# lcd-screen.net
KiCad netlist of a schematic drawn in EAGLE
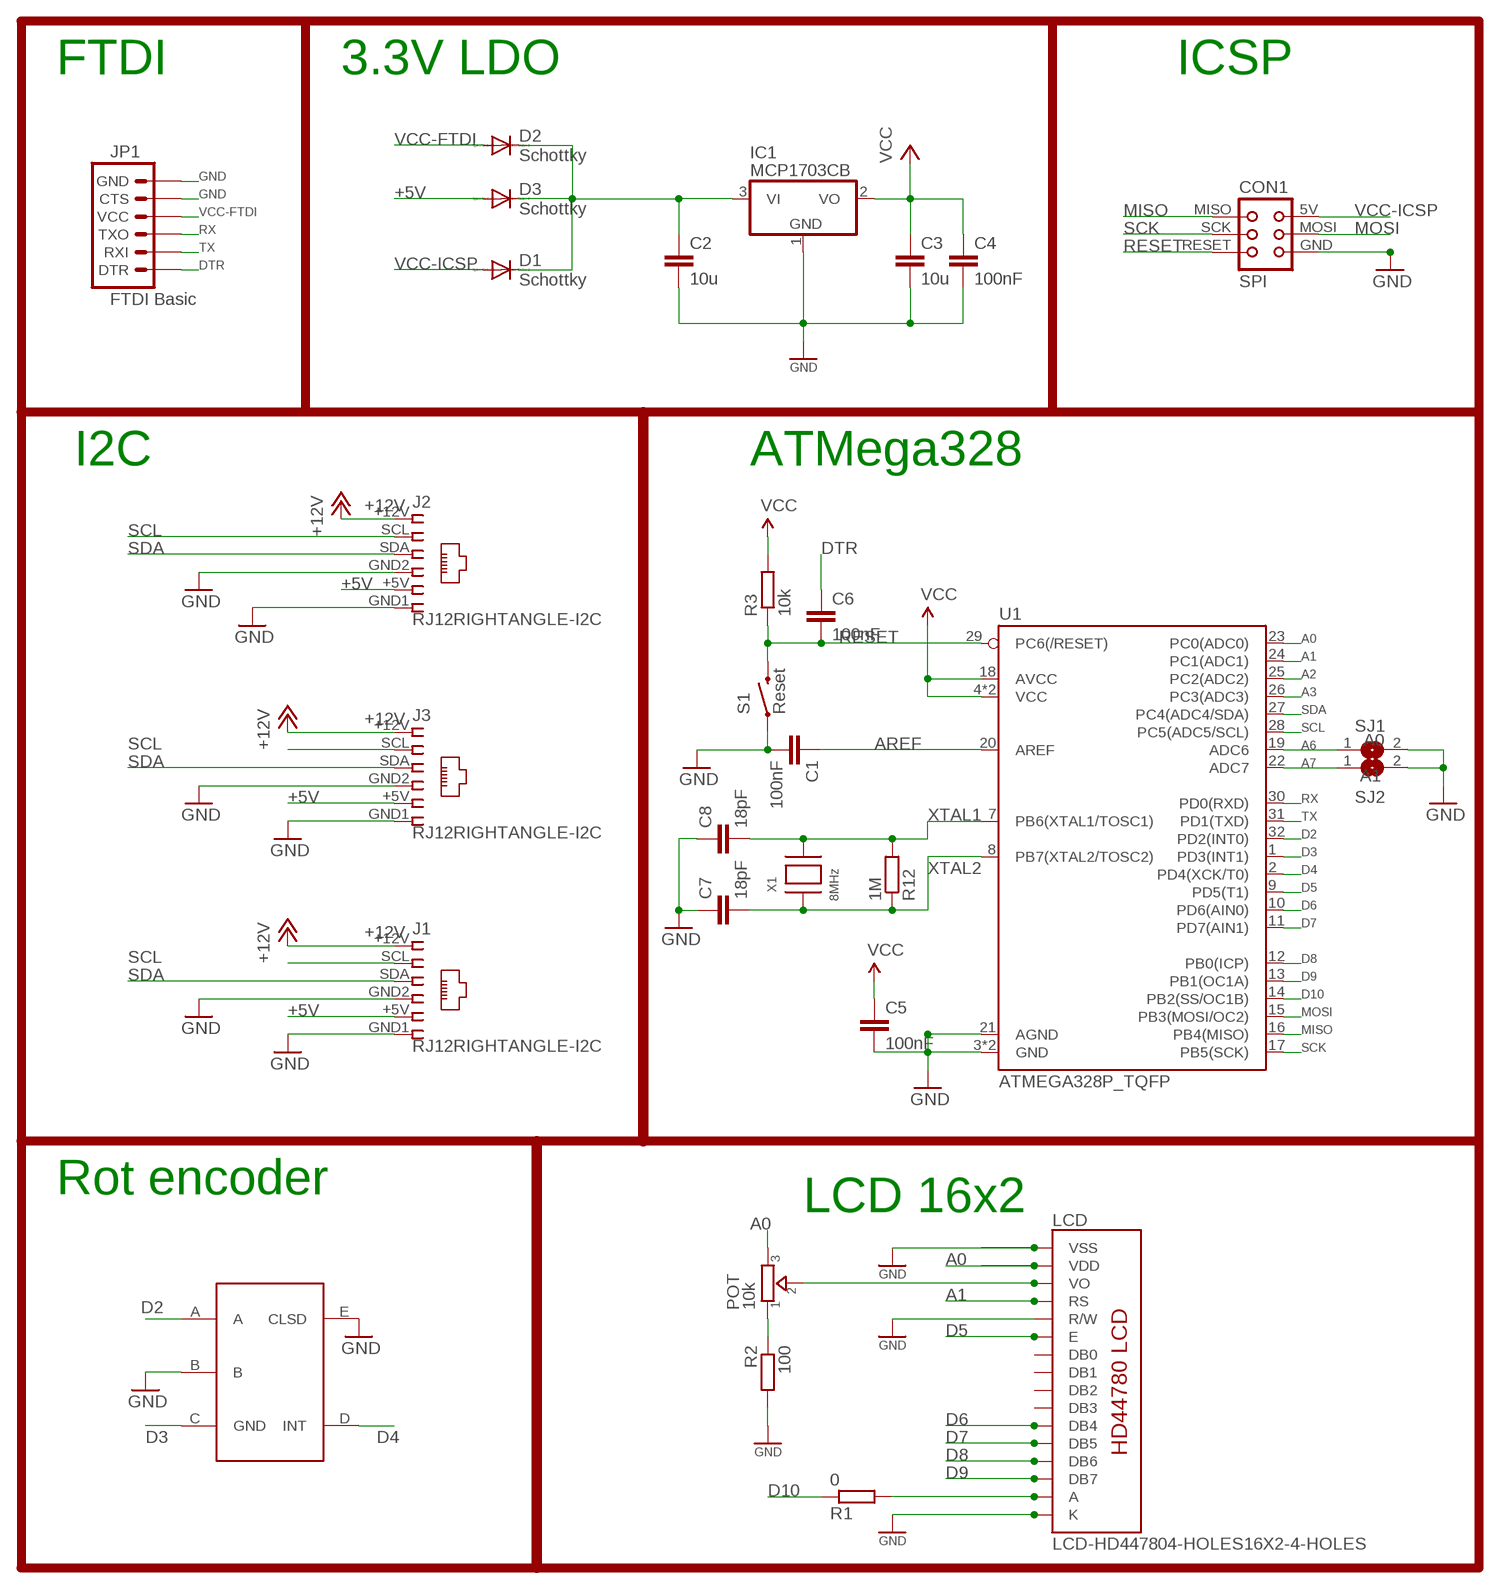
[diagram p0: schematic, sheet 1]

(export (version "E")
  (design (tool "Eeschema 10.0.6"))
  (components
    (comp (ref "C1")
      (value "100nF")
      (footprint "eagle-import:C0805K")
      (fields (field (name "MPN") "80-C1206C104K5R"))
      (libsource (lib "eagle-import") (part "C-EUC0805K"))
    )
    (comp (ref "C2")
      (value "10u")
      (footprint "eagle-import:C0805K")
      (fields (field (name "MPN") "77-VJ1206V106ZXQTBC"))
      (libsource (lib "eagle-import") (part "C-EUC0805K"))
    )
    (comp (ref "C3")
      (value "10u")
      (footprint "eagle-import:C0805K")
      (fields (field (name "MPN") "77-VJ1206V106ZXQTBC"))
      (libsource (lib "eagle-import") (part "C-EUC0805K"))
    )
    (comp (ref "C4")
      (value "100nF")
      (footprint "eagle-import:C0805K")
      (fields (field (name "MPN") "80-C1206C104K5R"))
      (libsource (lib "eagle-import") (part "C-EUC0805K"))
    )
    (comp (ref "C5")
      (value "100nF")
      (footprint "eagle-import:C0805K")
      (fields (field (name "MPN") "80-C1206C104K5R"))
      (libsource (lib "eagle-import") (part "C-EUC0805K"))
    )
    (comp (ref "C6")
      (value "100nF")
      (footprint "eagle-import:C0805K")
      (fields (field (name "MPN") "80-C1206C104K5R"))
      (libsource (lib "eagle-import") (part "C-EUC0805K"))
    )
    (comp (ref "C7")
      (value "18pF")
      (footprint "eagle-import:C0805K")
      (fields (field (name "MPN") "77-VJ1206A180JXXPBC"))
      (libsource (lib "eagle-import") (part "C-EUC0805K"))
    )
    (comp (ref "C8")
      (value "18pF")
      (footprint "eagle-import:C0805K")
      (fields (field (name "MPN") "77-VJ1206A180JXXPBC"))
      (libsource (lib "eagle-import") (part "C-EUC0805K"))
    )
    (comp (ref "CON1")
      (value "SPI")
      (footprint "eagle-import:TC2030-MCP")
      (libsource (lib "eagle-import") (part "TINYISPTAG"))
    )
    (comp (ref "D1")
      (value "Schottky")
      (footprint "eagle-import:SOD123")
      (fields (field (name "MPN") "621-1N5819HW-F"))
      (libsource (lib "eagle-import") (part "MBR0520LT"))
    )
    (comp (ref "D2")
      (value "Schottky")
      (footprint "eagle-import:SOD123")
      (fields (field (name "MPN") "621-1N5819HW-F"))
      (libsource (lib "eagle-import") (part "MBR0520LT"))
    )
    (comp (ref "D3")
      (value "Schottky")
      (footprint "eagle-import:SOD123")
      (fields (field (name "MPN") "621-1N5819HW-F"))
      (libsource (lib "eagle-import") (part "MBR0520LT"))
    )
    (comp (ref "IC1")
      (value "MCP1703CB")
      (footprint "eagle-import:SOT23")
      (libsource (lib "eagle-import") (part "MCP1703CB"))
    )
    (comp (ref "J1")
      (value "RJ12RIGHTANGLE-I2C")
      (footprint "eagle-import:RJ12-RIGHTANGLE-I2C")
      (libsource (lib "eagle-import") (part "RJ12RIGHTANGLE-I2C"))
    )
    (comp (ref "J2")
      (value "RJ12RIGHTANGLE-I2C")
      (footprint "eagle-import:RJ12-RIGHTANGLE-I2C")
      (libsource (lib "eagle-import") (part "RJ12RIGHTANGLE-I2C"))
    )
    (comp (ref "J3")
      (value "RJ12RIGHTANGLE-I2C")
      (footprint "eagle-import:RJ12-RIGHTANGLE-I2C")
      (libsource (lib "eagle-import") (part "RJ12RIGHTANGLE-I2C"))
    )
    (comp (ref "JP1")
      (value "FTDI Basic")
      (footprint "eagle-import:1X06")
      (libsource (lib "eagle-import") (part "ARDUINO_SERIAL_PROGRAMPTH"))
    )
    (comp (ref "LCD")
      (value "LCD-HD447804-HOLES16X2-4-HOLES")
      (footprint "eagle-import:LCD-16X2-4HOLES")
      (libsource (lib "eagle-import") (part "LCD-HD4478016X2-4-HOLES4-HOLES"))
    )
    (comp (ref "POT")
      (value "10k")
      (footprint "eagle-import:TRIMMER_3362P")
      (libsource (lib "eagle-import") (part "TRIMMER-3362P"))
    )
    (comp (ref "R1")
      (value "0")
      (footprint "eagle-import:R0805")
      (libsource (lib "eagle-import") (part "rcl_334_R-EU_R0805"))
    )
    (comp (ref "R2")
      (value "100")
      (footprint "eagle-import:R0805")
      (libsource (lib "eagle-import") (part "R-EU_R0805"))
    )
    (comp (ref "R3")
      (value "10k")
      (footprint "eagle-import:R0805")
      (libsource (lib "eagle-import") (part "R-EU_R0805"))
    )
    (comp (ref "R12")
      (value "1M")
      (footprint "eagle-import:R0805")
      (libsource (lib "eagle-import") (part "R-EU_R0805"))
    )
    (comp (ref "S1")
      (value "Reset")
      (footprint "eagle-import:TACTILE-SWITCH-SMD-ALT01")
      (libsource (lib "eagle-import") (part "SWITCH-MOMENTARY-2SMD-ALT01"))
    )
    (comp (ref "SJ1") (value "A0") (footprint "eagle-import:SJ") (libsource (lib "eagle-import") (part "SJ")))
    (comp (ref "SJ2") (value "A1") (footprint "eagle-import:SJ") (libsource (lib "eagle-import") (part "SJ")))
    (comp (ref "U$1")
      (value "EC11E")
      (footprint "eagle-import:EC11E")
      (libsource (lib "eagle-import") (part "EC11E"))
    )
    (comp (ref "U1")
      (value "ATMEGA328P_TQFP")
      (footprint "eagle-import:TQFP32-08")
      (libsource (lib "eagle-import") (part "ATMEGA328P_TQFP"))
    )
    (comp (ref "X1")
      (value "8MHz")
      (footprint "eagle-import:NX6035")
      (fields (field (name "MPN") "729-F60800010"))
      (libsource (lib "eagle-import") (part "XTALNX6035"))
    )
  )
  (nets
    (net (code "1") (name "+12V") (class "Default")
      (node (ref "J1") (pin "+12V") (pinfunction "1_+12V") (pintype "bidirectional"))
      (node (ref "J2") (pin "+12V") (pinfunction "1_+12V") (pintype "bidirectional"))
      (node (ref "J3") (pin "+12V") (pinfunction "1_+12V") (pintype "bidirectional"))
    )
    (net (code "2") (name "/+5V") (class "Default")
      (node (ref "D3") (pin "A") (pinfunction "A_A") (pintype "passive"))
      (node (ref "J1") (pin "+5V") (pinfunction "5_+5V") (pintype "bidirectional"))
      (node (ref "J2") (pin "+5V") (pinfunction "5_+5V") (pintype "bidirectional"))
      (node (ref "J3") (pin "+5V") (pinfunction "5_+5V") (pintype "bidirectional"))
    )
    (net (code "3") (name "/A0") (class "Default")
      (node (ref "LCD") (pin "2") (pinfunction "VDD_2") (pintype "power_in"))
      (node (ref "POT") (pin "3") (pinfunction "3_3") (pintype "passive"))
      (node (ref "U1") (pin "23") (pinfunction "PC0(ADC0)_23") (pintype "bidirectional"))
    )
    (net (code "4") (name "/A1") (class "Default")
      (node (ref "LCD") (pin "4") (pinfunction "RS_4") (pintype "input"))
      (node (ref "U1") (pin "24") (pinfunction "PC1(ADC1)_24") (pintype "bidirectional"))
    )
    (net (code "5") (name "/A2") (class "Default")
      (node (ref "U1") (pin "25") (pinfunction "PC2(ADC2)_25") (pintype "bidirectional"))
    )
    (net (code "6") (name "/A3") (class "Default")
      (node (ref "U1") (pin "26") (pinfunction "PC3(ADC3)_26") (pintype "bidirectional"))
    )
    (net (code "7") (name "/A6") (class "Default")
      (node (ref "SJ1") (pin "1") (pinfunction "1_1") (pintype "passive"))
      (node (ref "U1") (pin "19") (pinfunction "ADC6_19") (pintype "bidirectional"))
    )
    (net (code "8") (name "/A7") (class "Default")
      (node (ref "SJ2") (pin "1") (pinfunction "1_1") (pintype "passive"))
      (node (ref "U1") (pin "22") (pinfunction "ADC7_22") (pintype "bidirectional"))
    )
    (net (code "9") (name "/AREF") (class "Default")
      (node (ref "C1") (pin "1") (pinfunction "1_1") (pintype "passive"))
      (node (ref "U1") (pin "20") (pinfunction "AREF_20") (pintype "bidirectional"))
    )
    (net (code "10") (name "/D2") (class "Default")
      (node (ref "U$1") (pin "A") (pinfunction "A_A") (pintype "bidirectional"))
      (node (ref "U1") (pin "32") (pinfunction "PD2(INT0)_32") (pintype "bidirectional"))
    )
    (net (code "11") (name "/D3") (class "Default")
      (node (ref "U$1") (pin "C") (pinfunction "GND_C") (pintype "bidirectional"))
      (node (ref "U1") (pin "1") (pinfunction "PD3(INT1)_1") (pintype "bidirectional"))
    )
    (net (code "12") (name "/D4") (class "Default")
      (node (ref "U$1") (pin "D") (pinfunction "INT_D") (pintype "bidirectional"))
      (node (ref "U1") (pin "2") (pinfunction "PD4(XCK/T0)_2") (pintype "bidirectional"))
    )
    (net (code "13") (name "/D5") (class "Default")
      (node (ref "LCD") (pin "6") (pinfunction "E_6") (pintype "input"))
      (node (ref "U1") (pin "9") (pinfunction "PD5(T1)_9") (pintype "bidirectional"))
    )
    (net (code "14") (name "/D6") (class "Default")
      (node (ref "LCD") (pin "11") (pinfunction "DB4_11") (pintype "bidirectional"))
      (node (ref "U1") (pin "10") (pinfunction "PD6(AIN0)_10") (pintype "bidirectional"))
    )
    (net (code "15") (name "/D7") (class "Default")
      (node (ref "LCD") (pin "12") (pinfunction "DB5_12") (pintype "bidirectional"))
      (node (ref "U1") (pin "11") (pinfunction "PD7(AIN1)_11") (pintype "bidirectional"))
    )
    (net (code "16") (name "/D8") (class "Default")
      (node (ref "LCD") (pin "13") (pinfunction "DB6_13") (pintype "bidirectional"))
      (node (ref "U1") (pin "12") (pinfunction "PB0(ICP)_12") (pintype "bidirectional"))
    )
    (net (code "17") (name "/D9") (class "Default")
      (node (ref "LCD") (pin "14") (pinfunction "DB7_14") (pintype "bidirectional"))
      (node (ref "U1") (pin "13") (pinfunction "PB1(OC1A)_13") (pintype "bidirectional"))
    )
    (net (code "18") (name "/D10") (class "Default")
      (node (ref "R1") (pin "1") (pinfunction "1_1") (pintype "passive"))
      (node (ref "U1") (pin "14") (pinfunction "PB2(SS/OC1B)_14") (pintype "bidirectional"))
    )
    (net (code "19") (name "/DTR") (class "Default")
      (node (ref "C6") (pin "1") (pinfunction "1_1") (pintype "passive"))
      (node (ref "JP1") (pin "1") (pinfunction "DTR_1") (pintype "passive"))
    )
    (net (code "20") (name "/MISO") (class "Default")
      (node (ref "CON1") (pin "MISO") (pinfunction "MISO_MISO") (pintype "passive"))
      (node (ref "U1") (pin "16") (pinfunction "PB4(MISO)_16") (pintype "bidirectional"))
    )
    (net (code "21") (name "/MOSI") (class "Default")
      (node (ref "CON1") (pin "MOSI") (pinfunction "MOSI_MOSI") (pintype "passive"))
      (node (ref "U1") (pin "15") (pinfunction "PB3(MOSI/OC2)_15") (pintype "bidirectional"))
    )
    (net (code "22") (name "/RESET") (class "Default")
      (node (ref "C6") (pin "2") (pinfunction "2_2") (pintype "passive"))
      (node (ref "CON1") (pin "RESET") (pinfunction "RESET_RESET") (pintype "passive"))
      (node (ref "R3") (pin "1") (pinfunction "1_1") (pintype "passive"))
      (node (ref "S1") (pin "3") (pinfunction "2_3") (pintype "passive"))
      (node (ref "S1") (pin "4") (pinfunction "2_4") (pintype "passive"))
      (node (ref "U1") (pin "29") (pinfunction "PC6(/RESET)_29") (pintype "bidirectional"))
    )
    (net (code "23") (name "/RX") (class "Default")
      (node (ref "JP1") (pin "3") (pinfunction "TXO_3") (pintype "passive"))
      (node (ref "U1") (pin "30") (pinfunction "PD0(RXD)_30") (pintype "bidirectional"))
    )
    (net (code "24") (name "/SCK") (class "Default")
      (node (ref "CON1") (pin "SCK") (pinfunction "SCK_SCK") (pintype "passive"))
      (node (ref "U1") (pin "17") (pinfunction "PB5(SCK)_17") (pintype "bidirectional"))
    )
    (net (code "25") (name "/SCL") (class "Default")
      (node (ref "J1") (pin "SCL") (pinfunction "2_SCL") (pintype "bidirectional"))
      (node (ref "J2") (pin "SCL") (pinfunction "2_SCL") (pintype "bidirectional"))
      (node (ref "J3") (pin "SCL") (pinfunction "2_SCL") (pintype "bidirectional"))
      (node (ref "U1") (pin "28") (pinfunction "PC5(ADC5/SCL)_28") (pintype "bidirectional"))
    )
    (net (code "26") (name "/SDA") (class "Default")
      (node (ref "J1") (pin "SDA") (pinfunction "3_SDA") (pintype "bidirectional"))
      (node (ref "J2") (pin "SDA") (pinfunction "3_SDA") (pintype "bidirectional"))
      (node (ref "J3") (pin "SDA") (pinfunction "3_SDA") (pintype "bidirectional"))
      (node (ref "U1") (pin "27") (pinfunction "PC4(ADC4/SDA)_27") (pintype "bidirectional"))
    )
    (net (code "27") (name "/TX") (class "Default")
      (node (ref "JP1") (pin "2") (pinfunction "RXI_2") (pintype "passive"))
      (node (ref "U1") (pin "31") (pinfunction "PD1(TXD)_31") (pintype "bidirectional"))
    )
    (net (code "28") (name "/VCC-FTDI") (class "Default")
      (node (ref "D2") (pin "A") (pinfunction "A_A") (pintype "passive"))
      (node (ref "JP1") (pin "4") (pinfunction "VCC_4") (pintype "passive"))
    )
    (net (code "29") (name "/VCC-ICSP") (class "Default")
      (node (ref "CON1") (pin "5V") (pinfunction "VCC_5V") (pintype "passive"))
      (node (ref "D1") (pin "A") (pinfunction "A_A") (pintype "passive"))
    )
    (net (code "30") (name "/XTAL1") (class "Default")
      (node (ref "C8") (pin "2") (pinfunction "2_2") (pintype "passive"))
      (node (ref "R12") (pin "2") (pinfunction "2_2") (pintype "passive"))
      (node (ref "U1") (pin "7") (pinfunction "PB6(XTAL1/TOSC1)_7") (pintype "bidirectional"))
      (node (ref "X1") (pin "P$2") (pinfunction "P$2_P$2") (pintype "bidirectional"))
    )
    (net (code "31") (name "/XTAL2") (class "Default")
      (node (ref "C7") (pin "2") (pinfunction "2_2") (pintype "passive"))
      (node (ref "R12") (pin "1") (pinfunction "1_1") (pintype "passive"))
      (node (ref "U1") (pin "8") (pinfunction "PB7(XTAL2/TOSC2)_8") (pintype "bidirectional"))
      (node (ref "X1") (pin "P$1") (pinfunction "P$1_P$1") (pintype "bidirectional"))
    )
    (net (code "32") (name "GND") (class "Default")
      (node (ref "C1") (pin "2") (pinfunction "2_2") (pintype "passive"))
      (node (ref "C2") (pin "2") (pinfunction "2_2") (pintype "passive"))
      (node (ref "C3") (pin "2") (pinfunction "2_2") (pintype "passive"))
      (node (ref "C4") (pin "2") (pinfunction "2_2") (pintype "passive"))
      (node (ref "C5") (pin "2") (pinfunction "2_2") (pintype "passive"))
      (node (ref "C7") (pin "1") (pinfunction "1_1") (pintype "passive"))
      (node (ref "C8") (pin "1") (pinfunction "1_1") (pintype "passive"))
      (node (ref "CON1") (pin "GND") (pinfunction "GND_GND") (pintype "passive"))
      (node (ref "IC1") (pin "1") (pinfunction "GND_1") (pintype "passive"))
      (node (ref "J1") (pin "GND1") (pinfunction "6_GND1") (pintype "bidirectional"))
      (node (ref "J1") (pin "GND2") (pinfunction "4_GND2") (pintype "bidirectional"))
      (node (ref "J2") (pin "GND1") (pinfunction "6_GND1") (pintype "bidirectional"))
      (node (ref "J2") (pin "GND2") (pinfunction "4_GND2") (pintype "bidirectional"))
      (node (ref "J3") (pin "GND1") (pinfunction "6_GND1") (pintype "bidirectional"))
      (node (ref "J3") (pin "GND2") (pinfunction "4_GND2") (pintype "bidirectional"))
      (node (ref "JP1") (pin "5") (pinfunction "CTS_5") (pintype "passive"))
      (node (ref "JP1") (pin "6") (pinfunction "GND_6") (pintype "passive"))
      (node (ref "LCD") (pin "1") (pinfunction "VSS_1") (pintype "power_in"))
      (node (ref "LCD") (pin "16") (pinfunction "K_16") (pintype "power_in"))
      (node (ref "LCD") (pin "5") (pinfunction "R/W_5") (pintype "input"))
      (node (ref "R2") (pin "2") (pinfunction "2_2") (pintype "passive"))
      (node (ref "S1") (pin "1") (pinfunction "1_1") (pintype "passive"))
      (node (ref "S1") (pin "2") (pinfunction "1_2") (pintype "passive"))
      (node (ref "SJ1") (pin "2") (pinfunction "2_2") (pintype "passive"))
      (node (ref "SJ2") (pin "2") (pinfunction "2_2") (pintype "passive"))
      (node (ref "U$1") (pin "B") (pinfunction "B_B") (pintype "bidirectional"))
      (node (ref "U$1") (pin "E") (pinfunction "CLSD_E") (pintype "bidirectional"))
      (node (ref "U1") (pin "21") (pinfunction "AGND_21") (pintype "bidirectional"))
      (node (ref "U1") (pin "3") (pinfunction "GND_3") (pintype "bidirectional"))
      (node (ref "U1") (pin "5") (pinfunction "GND_5") (pintype "bidirectional"))
    )
    (net (code "33") (name "Net-(IC1-VI)") (class "Default")
      (node (ref "C2") (pin "1") (pinfunction "1_1") (pintype "passive"))
      (node (ref "D1") (pin "C") (pinfunction "C_C") (pintype "passive"))
      (node (ref "D2") (pin "C") (pinfunction "C_C") (pintype "passive"))
      (node (ref "D3") (pin "C") (pinfunction "C_C") (pintype "passive"))
      (node (ref "IC1") (pin "3") (pinfunction "VI_3") (pintype "input"))
    )
    (net (code "34") (name "Net-(LCD-A)") (class "Default")
      (node (ref "LCD") (pin "15") (pinfunction "A_15") (pintype "power_in"))
      (node (ref "R1") (pin "2") (pinfunction "2_2") (pintype "passive"))
    )
    (net (code "35") (name "Net-(LCD-VO)") (class "Default")
      (node (ref "LCD") (pin "3") (pinfunction "VO_3") (pintype "bidirectional"))
      (node (ref "POT") (pin "2") (pinfunction "2_2") (pintype "passive"))
    )
    (net (code "36") (name "Net-(POT-Pad1)") (class "Default")
      (node (ref "POT") (pin "1") (pinfunction "1_1") (pintype "passive"))
      (node (ref "R2") (pin "1") (pinfunction "1_1") (pintype "passive"))
    )
    (net (code "37") (name "VCC") (class "Default")
      (node (ref "C3") (pin "1") (pinfunction "1_1") (pintype "passive"))
      (node (ref "C4") (pin "1") (pinfunction "1_1") (pintype "passive"))
      (node (ref "C5") (pin "1") (pinfunction "1_1") (pintype "passive"))
      (node (ref "IC1") (pin "2") (pinfunction "VO_2") (pintype "passive"))
      (node (ref "R3") (pin "2") (pinfunction "2_2") (pintype "passive"))
      (node (ref "U1") (pin "18") (pinfunction "AVCC_18") (pintype "bidirectional"))
      (node (ref "U1") (pin "4") (pinfunction "VCC_4") (pintype "bidirectional"))
      (node (ref "U1") (pin "6") (pinfunction "VCC_6") (pintype "bidirectional"))
    )
    (net (code "38") (name "unconnected-(LCD-DB0-Pad7)") (class "Default")
      (node (ref "LCD") (pin "7") (pinfunction "DB0_7") (pintype "bidirectional"))
    )
    (net (code "39") (name "unconnected-(LCD-DB1-Pad8)") (class "Default")
      (node (ref "LCD") (pin "8") (pinfunction "DB1_8") (pintype "bidirectional"))
    )
    (net (code "40") (name "unconnected-(LCD-DB2-Pad9)") (class "Default")
      (node (ref "LCD") (pin "9") (pinfunction "DB2_9") (pintype "bidirectional"))
    )
    (net (code "41") (name "unconnected-(LCD-DB3-Pad10)") (class "Default")
      (node (ref "LCD") (pin "10") (pinfunction "DB3_10") (pintype "bidirectional"))
    )
  )
)
